# ETS2-Interface.net
KiCad netlist of a schematic drawn in EAGLE
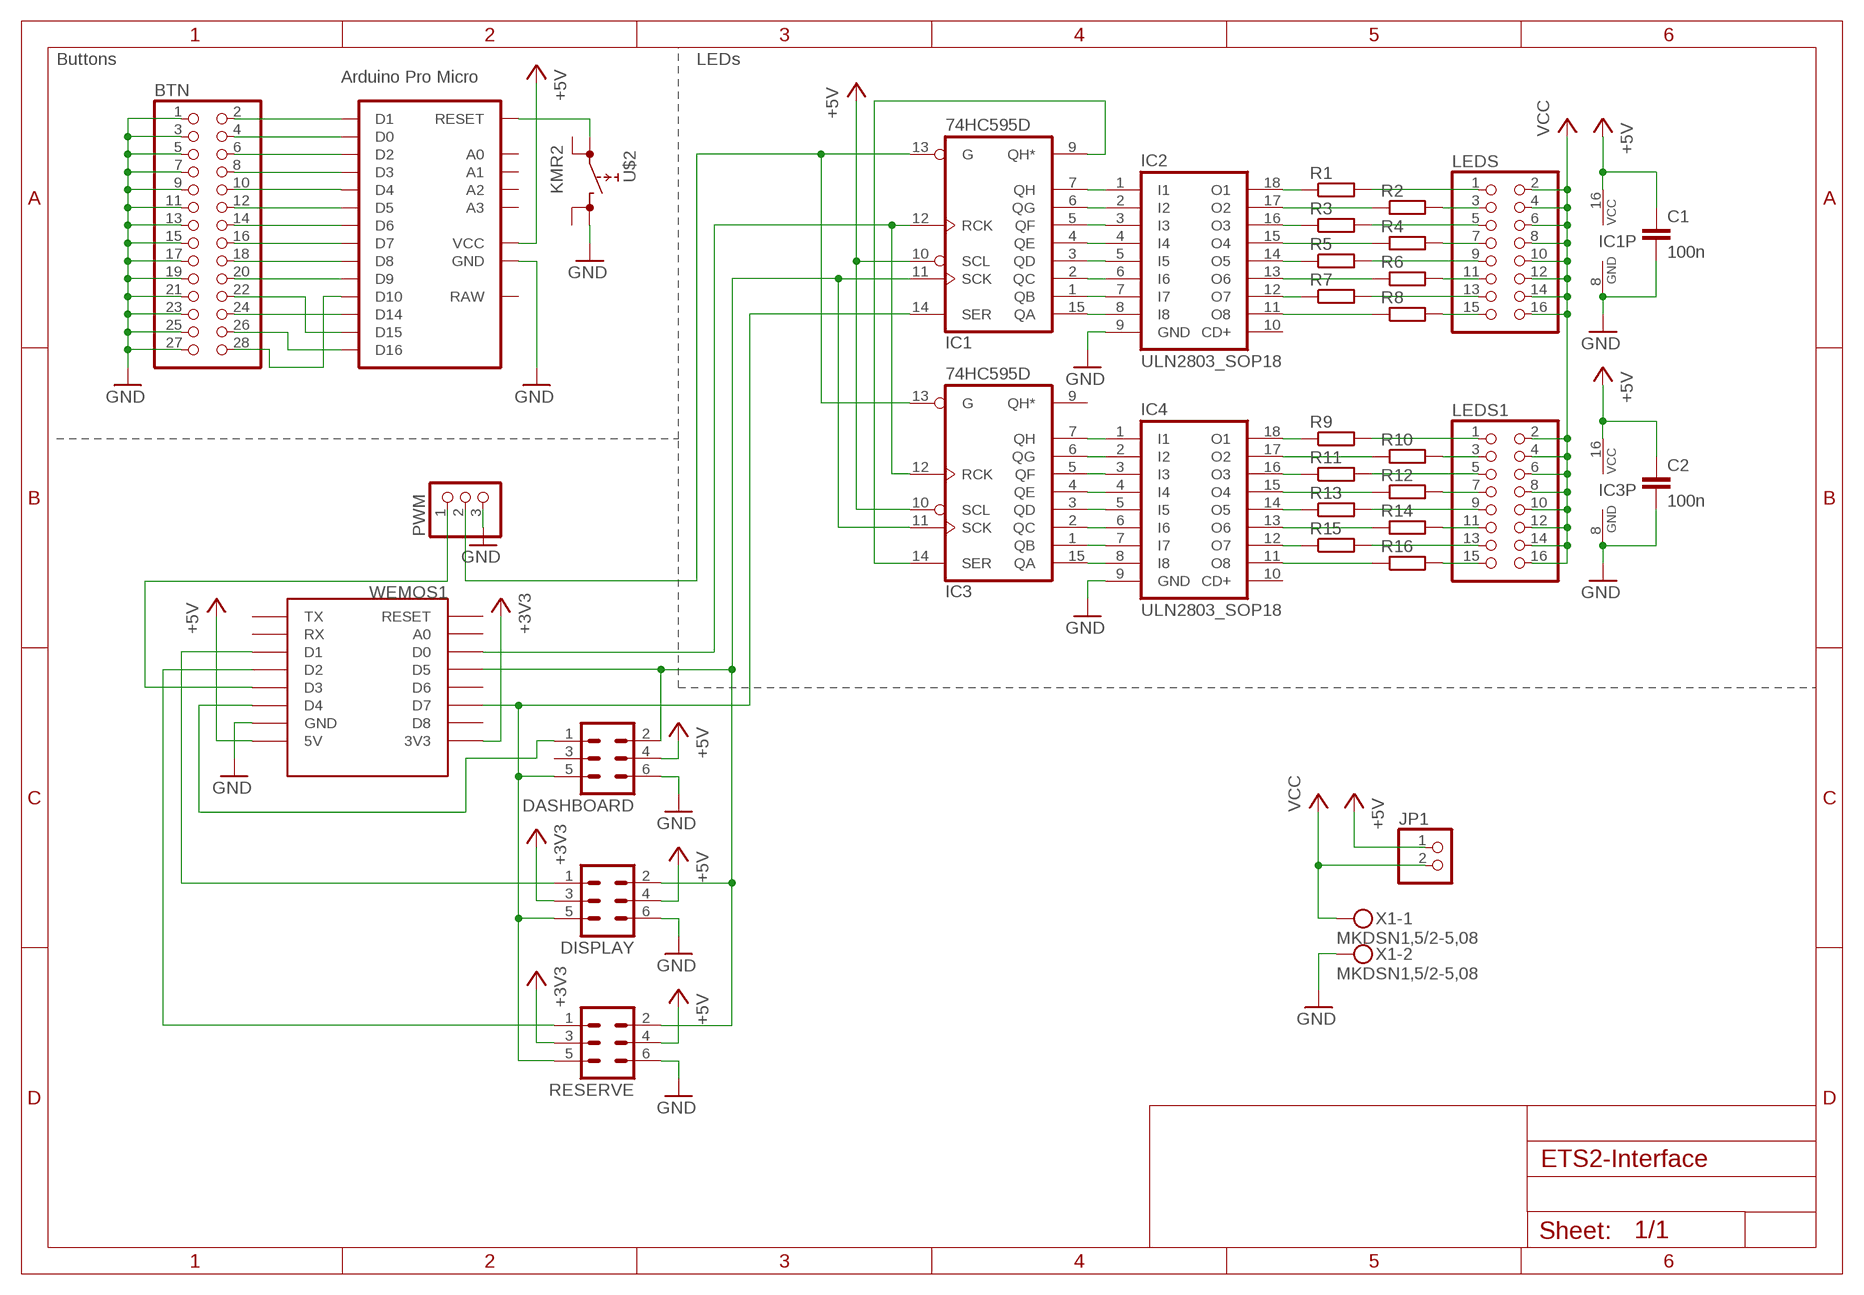
[diagram p0: schematic, sheet 1]

(export (version "E")
  (design (tool "Eeschema 10.0.6"))
  (components
    (comp (ref "BTN")
      (value "PINHD-2X14_2.54")
      (footprint "eagle-import:2X14")
      (libsource (lib "eagle-import") (part "PINHD-2X14_2.54"))
    )
    (comp (ref "C1")
      (value "100n")
      (footprint "eagle-import:C0805")
      (libsource (lib "eagle-import") (part "C-EUC0805"))
    )
    (comp (ref "C2")
      (value "100n")
      (footprint "eagle-import:C0805")
      (libsource (lib "eagle-import") (part "C-EUC0805"))
    )
    (comp (ref "DASHBOARD")
      (value "ML6")
      (footprint "eagle-import:ML6")
      (libsource (lib "eagle-import") (part "ML6"))
    )
    (comp (ref "DISPLAY")
      (value "ML6")
      (footprint "eagle-import:ML6")
      (libsource (lib "eagle-import") (part "ML6"))
    )
    (comp (ref "IC1")
      (value "74HC595D")
      (footprint "eagle-import:SO16")
      (libsource (lib "eagle-import") (part "74595DHC"))
    )
    (comp (ref "IC2")
      (value "ULN2803_SOP18")
      (footprint "eagle-import:SOP18")
      (libsource (lib "eagle-import") (part "ULN2803_SOP18"))
    )
    (comp (ref "IC3")
      (value "74HC595D")
      (footprint "eagle-import:SO16")
      (libsource (lib "eagle-import") (part "74595DHC"))
    )
    (comp (ref "IC4")
      (value "ULN2803_SOP18")
      (footprint "eagle-import:SOP18")
      (libsource (lib "eagle-import") (part "ULN2803_SOP18"))
    )
    (comp (ref "JP1")
      (value "PINHD-1X02_2.54-S")
      (footprint "eagle-import:1X02-S")
      (libsource (lib "eagle-import") (part "PINHD-1X02_2.54-S"))
    )
    (comp (ref "LEDS")
      (value "PINHD-2X08_2.54")
      (footprint "eagle-import:2X08")
      (libsource (lib "eagle-import") (part "PINHD-2X08_2.54"))
    )
    (comp (ref "LEDS1")
      (value "PINHD-2X08_2.54")
      (footprint "eagle-import:2X08")
      (libsource (lib "eagle-import") (part "PINHD-2X08_2.54"))
    )
    (comp (ref "PWM")
      (value "PINHD-1X03_2.54-S")
      (footprint "eagle-import:1X03-S")
      (libsource (lib "eagle-import") (part "PINHD-1X03_2.54-S"))
    )
    (comp (ref "R1")
      (value "R-EU_R0805")
      (footprint "eagle-import:R0805")
      (libsource (lib "eagle-import") (part "R-EU_R0805"))
    )
    (comp (ref "R2")
      (value "R-EU_R0805")
      (footprint "eagle-import:R0805")
      (libsource (lib "eagle-import") (part "R-EU_R0805"))
    )
    (comp (ref "R3")
      (value "R-EU_R0805")
      (footprint "eagle-import:R0805")
      (libsource (lib "eagle-import") (part "R-EU_R0805"))
    )
    (comp (ref "R4")
      (value "R-EU_R0805")
      (footprint "eagle-import:R0805")
      (libsource (lib "eagle-import") (part "R-EU_R0805"))
    )
    (comp (ref "R5")
      (value "R-EU_R0805")
      (footprint "eagle-import:R0805")
      (libsource (lib "eagle-import") (part "R-EU_R0805"))
    )
    (comp (ref "R6")
      (value "R-EU_R0805")
      (footprint "eagle-import:R0805")
      (libsource (lib "eagle-import") (part "R-EU_R0805"))
    )
    (comp (ref "R7")
      (value "R-EU_R0805")
      (footprint "eagle-import:R0805")
      (libsource (lib "eagle-import") (part "R-EU_R0805"))
    )
    (comp (ref "R8")
      (value "R-EU_R0805")
      (footprint "eagle-import:R0805")
      (libsource (lib "eagle-import") (part "R-EU_R0805"))
    )
    (comp (ref "R9")
      (value "R-EU_R0805")
      (footprint "eagle-import:R0805")
      (libsource (lib "eagle-import") (part "R-EU_R0805"))
    )
    (comp (ref "R10")
      (value "R-EU_R0805")
      (footprint "eagle-import:R0805")
      (libsource (lib "eagle-import") (part "R-EU_R0805"))
    )
    (comp (ref "R11")
      (value "R-EU_R0805")
      (footprint "eagle-import:R0805")
      (libsource (lib "eagle-import") (part "R-EU_R0805"))
    )
    (comp (ref "R12")
      (value "R-EU_R0805")
      (footprint "eagle-import:R0805")
      (libsource (lib "eagle-import") (part "R-EU_R0805"))
    )
    (comp (ref "R13")
      (value "R-EU_R0805")
      (footprint "eagle-import:R0805")
      (libsource (lib "eagle-import") (part "R-EU_R0805"))
    )
    (comp (ref "R14")
      (value "R-EU_R0805")
      (footprint "eagle-import:R0805")
      (libsource (lib "eagle-import") (part "R-EU_R0805"))
    )
    (comp (ref "R15")
      (value "R-EU_R0805")
      (footprint "eagle-import:R0805")
      (libsource (lib "eagle-import") (part "R-EU_R0805"))
    )
    (comp (ref "R16")
      (value "R-EU_R0805")
      (footprint "eagle-import:R0805")
      (libsource (lib "eagle-import") (part "R-EU_R0805"))
    )
    (comp (ref "RESERVE")
      (value "ML6")
      (footprint "eagle-import:ML6")
      (libsource (lib "eagle-import") (part "ML6"))
    )
    (comp (ref "U$1")
      (value "PRO-MICRO")
      (footprint "eagle-import:PRO-MICRO")
      (libsource (lib "eagle-import") (part "PRO-MICRO"))
    )
    (comp (ref "U$2")
      (value "KMR2")
      (footprint "eagle-import:KMR2")
      (libsource (lib "eagle-import") (part "KMR2"))
    )
    (comp (ref "WEMOS1")
      (value "WEMOS-D1-MINI")
      (footprint "eagle-import:WEMOS-D1-MINI")
      (libsource (lib "eagle-import") (part "WEMOS-D1-MINI"))
    )
    (comp (ref "X1")
      (value "MKDSN1,5/2-5,08")
      (footprint "eagle-import:MKDSN1,5_2-5,08")
      (libsource (lib "eagle-import") (part "MKDSN1,5/2-5,08"))
    )
  )
  (nets
    (net (code "1") (name "+3V3") (class "Default")
      (node (ref "DISPLAY") (pin "3") (pinfunction "3_3") (pintype "passive"))
      (node (ref "RESERVE") (pin "3") (pinfunction "3_3") (pintype "passive"))
      (node (ref "WEMOS1") (pin "3V3") (pinfunction "3V3_3V3") (pintype "bidirectional"))
    )
    (net (code "2") (name "+5V") (class "Default")
      (node (ref "C1") (pin "1") (pinfunction "1_1") (pintype "passive"))
      (node (ref "C2") (pin "1") (pinfunction "1_1") (pintype "passive"))
      (node (ref "DASHBOARD") (pin "4") (pinfunction "4_4") (pintype "passive"))
      (node (ref "DISPLAY") (pin "4") (pinfunction "4_4") (pintype "passive"))
      (node (ref "IC1") (pin "10") (pinfunction "SCL_10") (pintype "input"))
      (node (ref "IC1") (pin "16") (pinfunction "VCC_16") (pintype "power_in"))
      (node (ref "IC3") (pin "10") (pinfunction "SCL_10") (pintype "input"))
      (node (ref "IC3") (pin "16") (pinfunction "VCC_16") (pintype "power_in"))
      (node (ref "JP1") (pin "1") (pinfunction "1_1") (pintype "passive"))
      (node (ref "RESERVE") (pin "4") (pinfunction "4_4") (pintype "passive"))
      (node (ref "U$1") (pin "VCC") (pinfunction "VCC_VCC") (pintype "bidirectional"))
      (node (ref "WEMOS1") (pin "5V") (pinfunction "5V_5V") (pintype "bidirectional"))
    )
    (net (code "3") (name "GND") (class "Default")
      (node (ref "BTN") (pin "1") (pinfunction "1_1") (pintype "passive"))
      (node (ref "BTN") (pin "11") (pinfunction "11_11") (pintype "passive"))
      (node (ref "BTN") (pin "13") (pinfunction "13_13") (pintype "passive"))
      (node (ref "BTN") (pin "15") (pinfunction "15_15") (pintype "passive"))
      (node (ref "BTN") (pin "17") (pinfunction "17_17") (pintype "passive"))
      (node (ref "BTN") (pin "19") (pinfunction "19_19") (pintype "passive"))
      (node (ref "BTN") (pin "21") (pinfunction "21_21") (pintype "passive"))
      (node (ref "BTN") (pin "23") (pinfunction "23_23") (pintype "passive"))
      (node (ref "BTN") (pin "25") (pinfunction "25_25") (pintype "passive"))
      (node (ref "BTN") (pin "27") (pinfunction "27_27") (pintype "passive"))
      (node (ref "BTN") (pin "3") (pinfunction "3_3") (pintype "passive"))
      (node (ref "BTN") (pin "5") (pinfunction "5_5") (pintype "passive"))
      (node (ref "BTN") (pin "7") (pinfunction "7_7") (pintype "passive"))
      (node (ref "BTN") (pin "9") (pinfunction "9_9") (pintype "passive"))
      (node (ref "C1") (pin "2") (pinfunction "2_2") (pintype "passive"))
      (node (ref "C2") (pin "2") (pinfunction "2_2") (pintype "passive"))
      (node (ref "DASHBOARD") (pin "6") (pinfunction "6_6") (pintype "passive"))
      (node (ref "DISPLAY") (pin "6") (pinfunction "6_6") (pintype "passive"))
      (node (ref "IC1") (pin "8") (pinfunction "GND_8") (pintype "power_in"))
      (node (ref "IC2") (pin "9") (pinfunction "GND_9") (pintype "power_in"))
      (node (ref "IC3") (pin "8") (pinfunction "GND_8") (pintype "power_in"))
      (node (ref "IC4") (pin "9") (pinfunction "GND_9") (pintype "power_in"))
      (node (ref "PWM") (pin "3") (pinfunction "3_3") (pintype "passive"))
      (node (ref "RESERVE") (pin "6") (pinfunction "6_6") (pintype "passive"))
      (node (ref "U$1") (pin "GND") (pinfunction "GND_GND") (pintype "bidirectional"))
      (node (ref "U$1") (pin "GND1") (pinfunction "GND_GND1") (pintype "bidirectional"))
      (node (ref "U$1") (pin "GND2") (pinfunction "GND_GND2") (pintype "bidirectional"))
      (node (ref "U$2") (pin "3") (pinfunction "1_3") (pintype "passive"))
      (node (ref "WEMOS1") (pin "GND") (pinfunction "GND_GND") (pintype "bidirectional"))
      (node (ref "X1") (pin "2") (pinfunction "KL_2") (pintype "passive"))
    )
    (net (code "4") (name "Net-(BTN-Pad2)") (class "Default")
      (node (ref "BTN") (pin "2") (pinfunction "2_2") (pintype "passive"))
      (node (ref "U$1") (pin "D1") (pinfunction "D1_D1") (pintype "bidirectional"))
    )
    (net (code "5") (name "Net-(BTN-Pad4)") (class "Default")
      (node (ref "BTN") (pin "4") (pinfunction "4_4") (pintype "passive"))
      (node (ref "U$1") (pin "D0") (pinfunction "D0_D0") (pintype "bidirectional"))
    )
    (net (code "6") (name "Net-(BTN-Pad6)") (class "Default")
      (node (ref "BTN") (pin "6") (pinfunction "6_6") (pintype "passive"))
      (node (ref "U$1") (pin "D2") (pinfunction "D2_D2") (pintype "bidirectional"))
    )
    (net (code "7") (name "Net-(BTN-Pad8)") (class "Default")
      (node (ref "BTN") (pin "8") (pinfunction "8_8") (pintype "passive"))
      (node (ref "U$1") (pin "D3") (pinfunction "D3_D3") (pintype "bidirectional"))
    )
    (net (code "8") (name "Net-(BTN-Pad10)") (class "Default")
      (node (ref "BTN") (pin "10") (pinfunction "10_10") (pintype "passive"))
      (node (ref "U$1") (pin "D4") (pinfunction "D4_D4") (pintype "bidirectional"))
    )
    (net (code "9") (name "Net-(BTN-Pad12)") (class "Default")
      (node (ref "BTN") (pin "12") (pinfunction "12_12") (pintype "passive"))
      (node (ref "U$1") (pin "D5") (pinfunction "D5_D5") (pintype "bidirectional"))
    )
    (net (code "10") (name "Net-(BTN-Pad14)") (class "Default")
      (node (ref "BTN") (pin "14") (pinfunction "14_14") (pintype "passive"))
      (node (ref "U$1") (pin "D6") (pinfunction "D6_D6") (pintype "bidirectional"))
    )
    (net (code "11") (name "Net-(BTN-Pad16)") (class "Default")
      (node (ref "BTN") (pin "16") (pinfunction "16_16") (pintype "passive"))
      (node (ref "U$1") (pin "D7") (pinfunction "D7_D7") (pintype "bidirectional"))
    )
    (net (code "12") (name "Net-(BTN-Pad18)") (class "Default")
      (node (ref "BTN") (pin "18") (pinfunction "18_18") (pintype "passive"))
      (node (ref "U$1") (pin "D8") (pinfunction "D8_D8") (pintype "bidirectional"))
    )
    (net (code "13") (name "Net-(BTN-Pad20)") (class "Default")
      (node (ref "BTN") (pin "20") (pinfunction "20_20") (pintype "passive"))
      (node (ref "U$1") (pin "D9") (pinfunction "D9_D9") (pintype "bidirectional"))
    )
    (net (code "14") (name "Net-(BTN-Pad22)") (class "Default")
      (node (ref "BTN") (pin "22") (pinfunction "22_22") (pintype "passive"))
      (node (ref "U$1") (pin "D15") (pinfunction "D15_D15") (pintype "bidirectional"))
    )
    (net (code "15") (name "Net-(BTN-Pad24)") (class "Default")
      (node (ref "BTN") (pin "24") (pinfunction "24_24") (pintype "passive"))
      (node (ref "U$1") (pin "D14") (pinfunction "D14_D14") (pintype "bidirectional"))
    )
    (net (code "16") (name "Net-(BTN-Pad26)") (class "Default")
      (node (ref "BTN") (pin "26") (pinfunction "26_26") (pintype "passive"))
      (node (ref "U$1") (pin "D16") (pinfunction "D16_D16") (pintype "bidirectional"))
    )
    (net (code "17") (name "Net-(BTN-Pad28)") (class "Default")
      (node (ref "BTN") (pin "28") (pinfunction "28_28") (pintype "passive"))
      (node (ref "U$1") (pin "D10") (pinfunction "D10_D10") (pintype "bidirectional"))
    )
    (net (code "18") (name "Net-(DASHBOARD-Pad1)") (class "Default")
      (node (ref "DASHBOARD") (pin "1") (pinfunction "1_1") (pintype "passive"))
      (node (ref "WEMOS1") (pin "D4") (pinfunction "D4_D4") (pintype "bidirectional"))
    )
    (net (code "19") (name "Net-(DISPLAY-Pad1)") (class "Default")
      (node (ref "DISPLAY") (pin "1") (pinfunction "1_1") (pintype "passive"))
      (node (ref "WEMOS1") (pin "D1") (pinfunction "D1_D1") (pintype "bidirectional"))
    )
    (net (code "20") (name "Net-(IC1A-G)") (class "Default")
      (node (ref "IC1") (pin "13") (pinfunction "G_13") (pintype "input"))
      (node (ref "IC3") (pin "13") (pinfunction "G_13") (pintype "input"))
      (node (ref "PWM") (pin "2") (pinfunction "2_2") (pintype "passive"))
    )
    (net (code "21") (name "Net-(IC1A-QA)") (class "Default")
      (node (ref "IC1") (pin "15") (pinfunction "QA_15") (pintype "tri_state"))
      (node (ref "IC2") (pin "8") (pinfunction "I8_8") (pintype "input"))
    )
    (net (code "22") (name "Net-(IC1A-QB)") (class "Default")
      (node (ref "IC1") (pin "1") (pinfunction "QB_1") (pintype "tri_state"))
      (node (ref "IC2") (pin "7") (pinfunction "I7_7") (pintype "input"))
    )
    (net (code "23") (name "Net-(IC1A-QC)") (class "Default")
      (node (ref "IC1") (pin "2") (pinfunction "QC_2") (pintype "tri_state"))
      (node (ref "IC2") (pin "6") (pinfunction "I6_6") (pintype "input"))
    )
    (net (code "24") (name "Net-(IC1A-QD)") (class "Default")
      (node (ref "IC1") (pin "3") (pinfunction "QD_3") (pintype "tri_state"))
      (node (ref "IC2") (pin "5") (pinfunction "I5_5") (pintype "input"))
    )
    (net (code "25") (name "Net-(IC1A-QE)") (class "Default")
      (node (ref "IC1") (pin "4") (pinfunction "QE_4") (pintype "tri_state"))
      (node (ref "IC2") (pin "4") (pinfunction "I4_4") (pintype "input"))
    )
    (net (code "26") (name "Net-(IC1A-QF)") (class "Default")
      (node (ref "IC1") (pin "5") (pinfunction "QF_5") (pintype "tri_state"))
      (node (ref "IC2") (pin "3") (pinfunction "I3_3") (pintype "input"))
    )
    (net (code "27") (name "Net-(IC1A-QG)") (class "Default")
      (node (ref "IC1") (pin "6") (pinfunction "QG_6") (pintype "tri_state"))
      (node (ref "IC2") (pin "2") (pinfunction "I2_2") (pintype "input"))
    )
    (net (code "28") (name "Net-(IC1A-QH)") (class "Default")
      (node (ref "IC1") (pin "7") (pinfunction "QH_7") (pintype "tri_state"))
      (node (ref "IC2") (pin "1") (pinfunction "I1_1") (pintype "input"))
    )
    (net (code "29") (name "Net-(IC1A-QH*)") (class "Default")
      (node (ref "IC1") (pin "9") (pinfunction "QH*_9") (pintype "tri_state"))
      (node (ref "IC3") (pin "14") (pinfunction "SER_14") (pintype "input"))
    )
    (net (code "30") (name "Net-(IC1A-RCK)") (class "Default")
      (node (ref "IC1") (pin "12") (pinfunction "RCK_12") (pintype "input"))
      (node (ref "IC3") (pin "12") (pinfunction "RCK_12") (pintype "input"))
      (node (ref "WEMOS1") (pin "D0") (pinfunction "D0_D0") (pintype "bidirectional"))
    )
    (net (code "31") (name "Net-(IC1A-SCK)") (class "Default")
      (node (ref "DASHBOARD") (pin "2") (pinfunction "2_2") (pintype "passive"))
      (node (ref "DISPLAY") (pin "2") (pinfunction "2_2") (pintype "passive"))
      (node (ref "IC1") (pin "11") (pinfunction "SCK_11") (pintype "input"))
      (node (ref "IC3") (pin "11") (pinfunction "SCK_11") (pintype "input"))
      (node (ref "RESERVE") (pin "2") (pinfunction "2_2") (pintype "passive"))
      (node (ref "WEMOS1") (pin "D5") (pinfunction "D5_D5") (pintype "bidirectional"))
    )
    (net (code "32") (name "Net-(IC1A-SER)") (class "Default")
      (node (ref "DASHBOARD") (pin "5") (pinfunction "5_5") (pintype "passive"))
      (node (ref "DISPLAY") (pin "5") (pinfunction "5_5") (pintype "passive"))
      (node (ref "IC1") (pin "14") (pinfunction "SER_14") (pintype "input"))
      (node (ref "RESERVE") (pin "5") (pinfunction "5_5") (pintype "passive"))
      (node (ref "WEMOS1") (pin "D7") (pinfunction "D7_D7") (pintype "bidirectional"))
    )
    (net (code "33") (name "Net-(IC2-O1)") (class "Default")
      (node (ref "IC2") (pin "18") (pinfunction "O1_18") (pintype "open_collector"))
      (node (ref "R1") (pin "1") (pinfunction "1_1") (pintype "passive"))
    )
    (net (code "34") (name "Net-(IC2-O2)") (class "Default")
      (node (ref "IC2") (pin "17") (pinfunction "O2_17") (pintype "open_collector"))
      (node (ref "R2") (pin "1") (pinfunction "1_1") (pintype "passive"))
    )
    (net (code "35") (name "Net-(IC2-O3)") (class "Default")
      (node (ref "IC2") (pin "16") (pinfunction "O3_16") (pintype "open_collector"))
      (node (ref "R3") (pin "1") (pinfunction "1_1") (pintype "passive"))
    )
    (net (code "36") (name "Net-(IC2-O4)") (class "Default")
      (node (ref "IC2") (pin "15") (pinfunction "O4_15") (pintype "open_collector"))
      (node (ref "R4") (pin "1") (pinfunction "1_1") (pintype "passive"))
    )
    (net (code "37") (name "Net-(IC2-O5)") (class "Default")
      (node (ref "IC2") (pin "14") (pinfunction "O5_14") (pintype "open_collector"))
      (node (ref "R5") (pin "1") (pinfunction "1_1") (pintype "passive"))
    )
    (net (code "38") (name "Net-(IC2-O6)") (class "Default")
      (node (ref "IC2") (pin "13") (pinfunction "O6_13") (pintype "open_collector"))
      (node (ref "R6") (pin "1") (pinfunction "1_1") (pintype "passive"))
    )
    (net (code "39") (name "Net-(IC2-O7)") (class "Default")
      (node (ref "IC2") (pin "12") (pinfunction "O7_12") (pintype "open_collector"))
      (node (ref "R7") (pin "1") (pinfunction "1_1") (pintype "passive"))
    )
    (net (code "40") (name "Net-(IC2-O8)") (class "Default")
      (node (ref "IC2") (pin "11") (pinfunction "O8_11") (pintype "open_collector"))
      (node (ref "R8") (pin "1") (pinfunction "1_1") (pintype "passive"))
    )
    (net (code "41") (name "Net-(IC3A-QA)") (class "Default")
      (node (ref "IC3") (pin "15") (pinfunction "QA_15") (pintype "tri_state"))
      (node (ref "IC4") (pin "8") (pinfunction "I8_8") (pintype "input"))
    )
    (net (code "42") (name "Net-(IC3A-QB)") (class "Default")
      (node (ref "IC3") (pin "1") (pinfunction "QB_1") (pintype "tri_state"))
      (node (ref "IC4") (pin "7") (pinfunction "I7_7") (pintype "input"))
    )
    (net (code "43") (name "Net-(IC3A-QC)") (class "Default")
      (node (ref "IC3") (pin "2") (pinfunction "QC_2") (pintype "tri_state"))
      (node (ref "IC4") (pin "6") (pinfunction "I6_6") (pintype "input"))
    )
    (net (code "44") (name "Net-(IC3A-QD)") (class "Default")
      (node (ref "IC3") (pin "3") (pinfunction "QD_3") (pintype "tri_state"))
      (node (ref "IC4") (pin "5") (pinfunction "I5_5") (pintype "input"))
    )
    (net (code "45") (name "Net-(IC3A-QE)") (class "Default")
      (node (ref "IC3") (pin "4") (pinfunction "QE_4") (pintype "tri_state"))
      (node (ref "IC4") (pin "4") (pinfunction "I4_4") (pintype "input"))
    )
    (net (code "46") (name "Net-(IC3A-QF)") (class "Default")
      (node (ref "IC3") (pin "5") (pinfunction "QF_5") (pintype "tri_state"))
      (node (ref "IC4") (pin "3") (pinfunction "I3_3") (pintype "input"))
    )
    (net (code "47") (name "Net-(IC3A-QG)") (class "Default")
      (node (ref "IC3") (pin "6") (pinfunction "QG_6") (pintype "tri_state"))
      (node (ref "IC4") (pin "2") (pinfunction "I2_2") (pintype "input"))
    )
    (net (code "48") (name "Net-(IC3A-QH)") (class "Default")
      (node (ref "IC3") (pin "7") (pinfunction "QH_7") (pintype "tri_state"))
      (node (ref "IC4") (pin "1") (pinfunction "I1_1") (pintype "input"))
    )
    (net (code "49") (name "Net-(IC4-O1)") (class "Default")
      (node (ref "IC4") (pin "18") (pinfunction "O1_18") (pintype "open_collector"))
      (node (ref "R9") (pin "1") (pinfunction "1_1") (pintype "passive"))
    )
    (net (code "50") (name "Net-(IC4-O2)") (class "Default")
      (node (ref "IC4") (pin "17") (pinfunction "O2_17") (pintype "open_collector"))
      (node (ref "R10") (pin "1") (pinfunction "1_1") (pintype "passive"))
    )
    (net (code "51") (name "Net-(IC4-O3)") (class "Default")
      (node (ref "IC4") (pin "16") (pinfunction "O3_16") (pintype "open_collector"))
      (node (ref "R11") (pin "1") (pinfunction "1_1") (pintype "passive"))
    )
    (net (code "52") (name "Net-(IC4-O4)") (class "Default")
      (node (ref "IC4") (pin "15") (pinfunction "O4_15") (pintype "open_collector"))
      (node (ref "R12") (pin "1") (pinfunction "1_1") (pintype "passive"))
    )
    (net (code "53") (name "Net-(IC4-O5)") (class "Default")
      (node (ref "IC4") (pin "14") (pinfunction "O5_14") (pintype "open_collector"))
      (node (ref "R13") (pin "1") (pinfunction "1_1") (pintype "passive"))
    )
    (net (code "54") (name "Net-(IC4-O6)") (class "Default")
      (node (ref "IC4") (pin "13") (pinfunction "O6_13") (pintype "open_collector"))
      (node (ref "R14") (pin "1") (pinfunction "1_1") (pintype "passive"))
    )
    (net (code "55") (name "Net-(IC4-O7)") (class "Default")
      (node (ref "IC4") (pin "12") (pinfunction "O7_12") (pintype "open_collector"))
      (node (ref "R15") (pin "1") (pinfunction "1_1") (pintype "passive"))
    )
    (net (code "56") (name "Net-(IC4-O8)") (class "Default")
      (node (ref "IC4") (pin "11") (pinfunction "O8_11") (pintype "open_collector"))
      (node (ref "R16") (pin "1") (pinfunction "1_1") (pintype "passive"))
    )
    (net (code "57") (name "Net-(LEDS-Pad1)") (class "Default")
      (node (ref "LEDS") (pin "1") (pinfunction "1_1") (pintype "passive"))
      (node (ref "R1") (pin "2") (pinfunction "2_2") (pintype "passive"))
    )
    (net (code "58") (name "Net-(LEDS-Pad3)") (class "Default")
      (node (ref "LEDS") (pin "3") (pinfunction "3_3") (pintype "passive"))
      (node (ref "R2") (pin "2") (pinfunction "2_2") (pintype "passive"))
    )
    (net (code "59") (name "Net-(LEDS-Pad5)") (class "Default")
      (node (ref "LEDS") (pin "5") (pinfunction "5_5") (pintype "passive"))
      (node (ref "R3") (pin "2") (pinfunction "2_2") (pintype "passive"))
    )
    (net (code "60") (name "Net-(LEDS-Pad7)") (class "Default")
      (node (ref "LEDS") (pin "7") (pinfunction "7_7") (pintype "passive"))
      (node (ref "R4") (pin "2") (pinfunction "2_2") (pintype "passive"))
    )
    (net (code "61") (name "Net-(LEDS-Pad9)") (class "Default")
      (node (ref "LEDS") (pin "9") (pinfunction "9_9") (pintype "passive"))
      (node (ref "R5") (pin "2") (pinfunction "2_2") (pintype "passive"))
    )
    (net (code "62") (name "Net-(LEDS-Pad11)") (class "Default")
      (node (ref "LEDS") (pin "11") (pinfunction "11_11") (pintype "passive"))
      (node (ref "R6") (pin "2") (pinfunction "2_2") (pintype "passive"))
    )
    (net (code "63") (name "Net-(LEDS-Pad13)") (class "Default")
      (node (ref "LEDS") (pin "13") (pinfunction "13_13") (pintype "passive"))
      (node (ref "R7") (pin "2") (pinfunction "2_2") (pintype "passive"))
    )
    (net (code "64") (name "Net-(LEDS-Pad15)") (class "Default")
      (node (ref "LEDS") (pin "15") (pinfunction "15_15") (pintype "passive"))
      (node (ref "R8") (pin "2") (pinfunction "2_2") (pintype "passive"))
    )
    (net (code "65") (name "Net-(LEDS1-Pad1)") (class "Default")
      (node (ref "LEDS1") (pin "1") (pinfunction "1_1") (pintype "passive"))
      (node (ref "R9") (pin "2") (pinfunction "2_2") (pintype "passive"))
    )
    (net (code "66") (name "Net-(LEDS1-Pad3)") (class "Default")
      (node (ref "LEDS1") (pin "3") (pinfunction "3_3") (pintype "passive"))
      (node (ref "R10") (pin "2") (pinfunction "2_2") (pintype "passive"))
    )
    (net (code "67") (name "Net-(LEDS1-Pad5)") (class "Default")
      (node (ref "LEDS1") (pin "5") (pinfunction "5_5") (pintype "passive"))
      (node (ref "R11") (pin "2") (pinfunction "2_2") (pintype "passive"))
    )
    (net (code "68") (name "Net-(LEDS1-Pad7)") (class "Default")
      (node (ref "LEDS1") (pin "7") (pinfunction "7_7") (pintype "passive"))
      (node (ref "R12") (pin "2") (pinfunction "2_2") (pintype "passive"))
    )
    (net (code "69") (name "Net-(LEDS1-Pad9)") (class "Default")
      (node (ref "LEDS1") (pin "9") (pinfunction "9_9") (pintype "passive"))
      (node (ref "R13") (pin "2") (pinfunction "2_2") (pintype "passive"))
    )
    (net (code "70") (name "Net-(LEDS1-Pad11)") (class "Default")
      (node (ref "LEDS1") (pin "11") (pinfunction "11_11") (pintype "passive"))
      (node (ref "R14") (pin "2") (pinfunction "2_2") (pintype "passive"))
    )
    (net (code "71") (name "Net-(LEDS1-Pad13)") (class "Default")
      (node (ref "LEDS1") (pin "13") (pinfunction "13_13") (pintype "passive"))
      (node (ref "R15") (pin "2") (pinfunction "2_2") (pintype "passive"))
    )
    (net (code "72") (name "Net-(LEDS1-Pad15)") (class "Default")
      (node (ref "LEDS1") (pin "15") (pinfunction "15_15") (pintype "passive"))
      (node (ref "R16") (pin "2") (pinfunction "2_2") (pintype "passive"))
    )
    (net (code "73") (name "Net-(PWM-Pad1)") (class "Default")
      (node (ref "PWM") (pin "1") (pinfunction "1_1") (pintype "passive"))
      (node (ref "WEMOS1") (pin "D3") (pinfunction "D3_D3") (pintype "bidirectional"))
    )
    (net (code "74") (name "Net-(RESERVE-Pad1)") (class "Default")
      (node (ref "RESERVE") (pin "1") (pinfunction "1_1") (pintype "passive"))
      (node (ref "WEMOS1") (pin "D2") (pinfunction "D2_D2") (pintype "bidirectional"))
    )
    (net (code "75") (name "Net-(U$1-PadRESET)") (class "Default")
      (node (ref "U$1") (pin "RESET") (pinfunction "RESET_RESET") (pintype "bidirectional"))
      (node (ref "U$2") (pin "1") (pinfunction "0_1") (pintype "passive"))
    )
    (net (code "76") (name "VCC") (class "Default")
      (node (ref "JP1") (pin "2") (pinfunction "2_2") (pintype "passive"))
      (node (ref "LEDS") (pin "10") (pinfunction "10_10") (pintype "passive"))
      (node (ref "LEDS") (pin "12") (pinfunction "12_12") (pintype "passive"))
      (node (ref "LEDS") (pin "14") (pinfunction "14_14") (pintype "passive"))
      (node (ref "LEDS") (pin "16") (pinfunction "16_16") (pintype "passive"))
      (node (ref "LEDS") (pin "2") (pinfunction "2_2") (pintype "passive"))
      (node (ref "LEDS") (pin "4") (pinfunction "4_4") (pintype "passive"))
      (node (ref "LEDS") (pin "6") (pinfunction "6_6") (pintype "passive"))
      (node (ref "LEDS") (pin "8") (pinfunction "8_8") (pintype "passive"))
      (node (ref "LEDS1") (pin "10") (pinfunction "10_10") (pintype "passive"))
      (node (ref "LEDS1") (pin "12") (pinfunction "12_12") (pintype "passive"))
      (node (ref "LEDS1") (pin "14") (pinfunction "14_14") (pintype "passive"))
      (node (ref "LEDS1") (pin "16") (pinfunction "16_16") (pintype "passive"))
      (node (ref "LEDS1") (pin "2") (pinfunction "2_2") (pintype "passive"))
      (node (ref "LEDS1") (pin "4") (pinfunction "4_4") (pintype "passive"))
      (node (ref "LEDS1") (pin "6") (pinfunction "6_6") (pintype "passive"))
      (node (ref "LEDS1") (pin "8") (pinfunction "8_8") (pintype "passive"))
      (node (ref "X1") (pin "1") (pinfunction "KL_1") (pintype "passive"))
    )
    (net (code "77") (name "unconnected-(DASHBOARD-Pad3)") (class "Default")
      (node (ref "DASHBOARD") (pin "3") (pinfunction "3_3") (pintype "passive"))
    )
    (net (code "78") (name "unconnected-(IC2-CD+-Pad10)") (class "Default")
      (node (ref "IC2") (pin "10") (pinfunction "CD+_10") (pintype "passive"))
    )
    (net (code "79") (name "unconnected-(IC3A-QH*-Pad9)") (class "Default")
      (node (ref "IC3") (pin "9") (pinfunction "QH*_9") (pintype "tri_state"))
    )
    (net (code "80") (name "unconnected-(IC4-CD+-Pad10)") (class "Default")
      (node (ref "IC4") (pin "10") (pinfunction "CD+_10") (pintype "passive"))
    )
    (net (code "81") (name "unconnected-(U$1-PadA0)") (class "Default")
      (node (ref "U$1") (pin "A0") (pinfunction "A0_A0") (pintype "bidirectional"))
    )
    (net (code "82") (name "unconnected-(U$1-PadA1)") (class "Default")
      (node (ref "U$1") (pin "A1") (pinfunction "A1_A1") (pintype "bidirectional"))
    )
    (net (code "83") (name "unconnected-(U$1-PadA2)") (class "Default")
      (node (ref "U$1") (pin "A2") (pinfunction "A2_A2") (pintype "bidirectional"))
    )
    (net (code "84") (name "unconnected-(U$1-PadA3)") (class "Default")
      (node (ref "U$1") (pin "A3") (pinfunction "A3_A3") (pintype "bidirectional"))
    )
    (net (code "85") (name "unconnected-(U$1-PadRAW)") (class "Default")
      (node (ref "U$1") (pin "RAW") (pinfunction "RAW_RAW") (pintype "bidirectional"))
    )
    (net (code "86") (name "unconnected-(U$2-0-Pad2)") (class "Default")
      (node (ref "U$2") (pin "2") (pinfunction "0_2") (pintype "passive"))
    )
    (net (code "87") (name "unconnected-(U$2-1-Pad4)") (class "Default")
      (node (ref "U$2") (pin "4") (pinfunction "1_4") (pintype "passive"))
    )
    (net (code "88") (name "unconnected-(WEMOS1-PadA0)") (class "Default")
      (node (ref "WEMOS1") (pin "A0") (pinfunction "A0_A0") (pintype "bidirectional"))
    )
    (net (code "89") (name "unconnected-(WEMOS1-PadD6)") (class "Default")
      (node (ref "WEMOS1") (pin "D6") (pinfunction "D6_D6") (pintype "bidirectional"))
    )
    (net (code "90") (name "unconnected-(WEMOS1-PadD8)") (class "Default")
      (node (ref "WEMOS1") (pin "D8") (pinfunction "D8_D8") (pintype "bidirectional"))
    )
    (net (code "91") (name "unconnected-(WEMOS1-PadRESET)") (class "Default")
      (node (ref "WEMOS1") (pin "RESET") (pinfunction "RESET_RESET") (pintype "bidirectional"))
    )
    (net (code "92") (name "unconnected-(WEMOS1-PadRX)") (class "Default")
      (node (ref "WEMOS1") (pin "RX") (pinfunction "RX_RX") (pintype "bidirectional"))
    )
    (net (code "93") (name "unconnected-(WEMOS1-PadTX)") (class "Default")
      (node (ref "WEMOS1") (pin "TX") (pinfunction "TX_TX") (pintype "bidirectional"))
    )
  )
)
